# Integrated_Preamp_Sch.net
KiCad netlist of a schematic drawn in Altium Designer
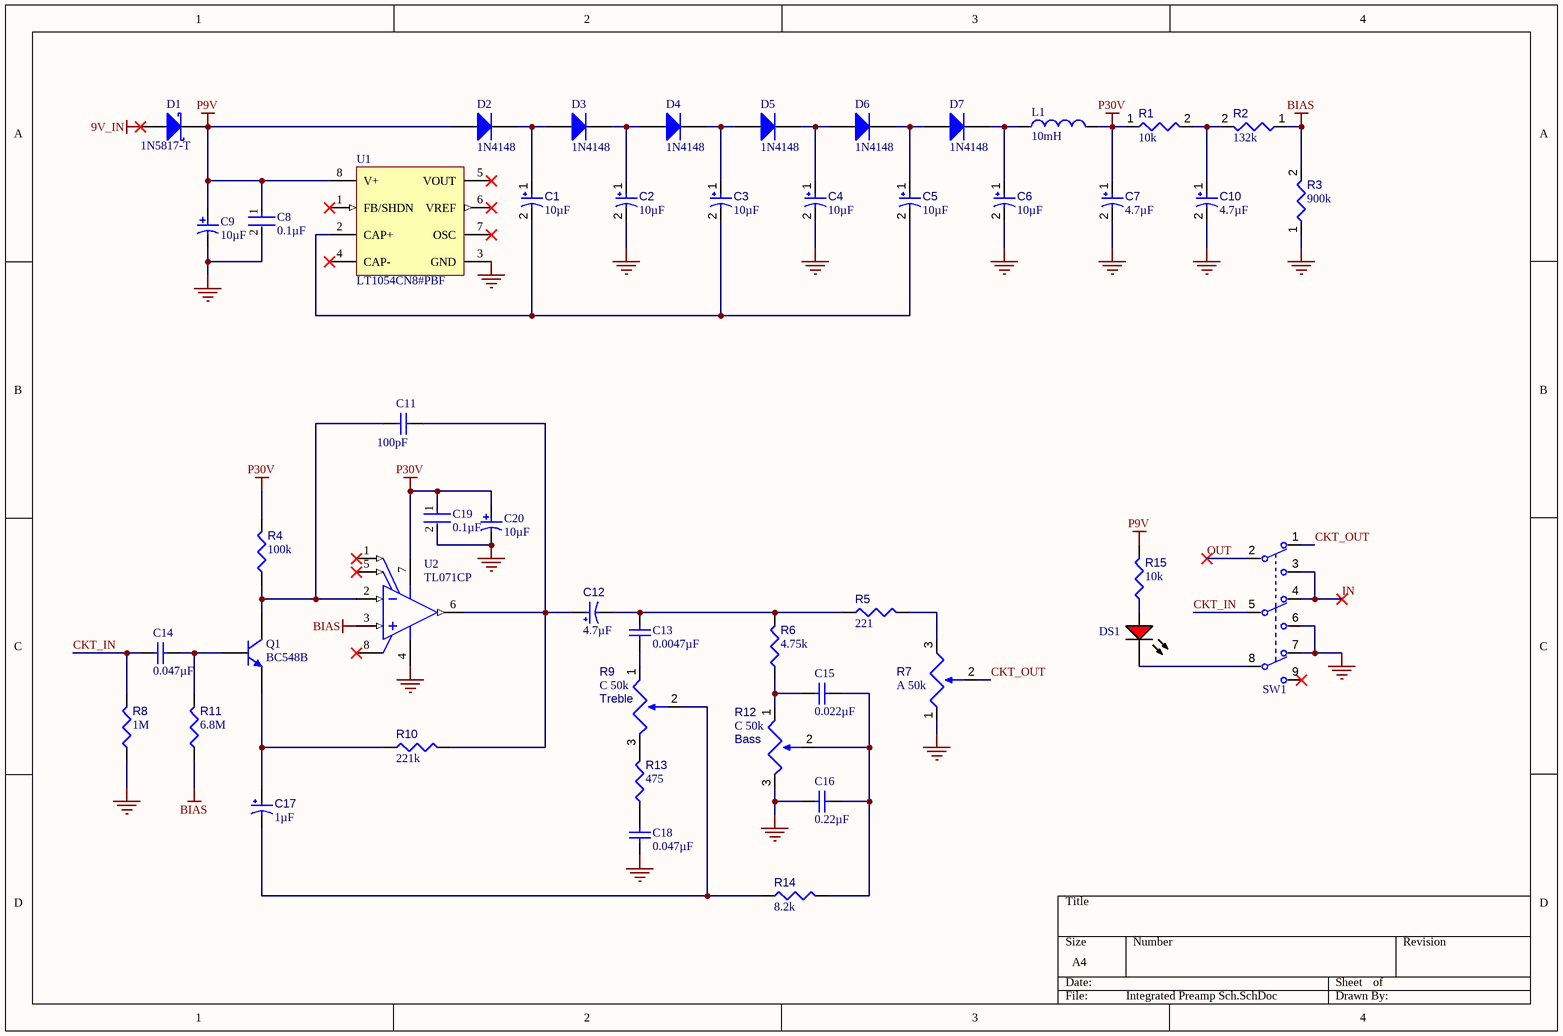
[diagram p0: Integrated Preamp Sch.SchDoc]

(export (version "E")
  (design (tool "Eeschema 10.0.6"))
  (components
    (comp (ref "C1")
      (value "10µF")
      (footprint "CAPPR55-200-1100X500X1200")
      (description "Aluminum Electrolytic Capacitor, 10 uF, +/- 20%, 50 V, -40 to 85 degC, 2-Pin THD, RoHS, Bulk")
      (fields (field (name "MANUFACTURER") "Panasonic") (field (name "TOLERANCE") "20%"))
      (libsource (lib "Andy R - Ferris State University") (part "CAP-P-2"))
    )
    (comp (ref "C2")
      (value "10µF")
      (footprint "CAPPR55-200-1100X500X1200")
      (description "Aluminum Electrolytic Capacitor, 10 uF, +/- 20%, 50 V, -40 to 85 degC, 2-Pin THD, RoHS, Bulk")
      (fields (field (name "MANUFACTURER") "Panasonic") (field (name "TOLERANCE") "20%"))
      (libsource (lib "Andy R - Ferris State University") (part "CAP-P-2"))
    )
    (comp (ref "C3")
      (value "10µF")
      (footprint "CAPPR55-200-1100X500X1200")
      (description "Aluminum Electrolytic Capacitor, 10 uF, +/- 20%, 50 V, -40 to 85 degC, 2-Pin THD, RoHS, Bulk")
      (fields (field (name "MANUFACTURER") "Panasonic") (field (name "TOLERANCE") "20%"))
      (libsource (lib "Andy R - Ferris State University") (part "CAP-P-2"))
    )
    (comp (ref "C4")
      (value "10µF")
      (footprint "CAPPR55-200-1100X500X1200")
      (description "Aluminum Electrolytic Capacitor, 10 uF, +/- 20%, 50 V, -40 to 85 degC, 2-Pin THD, RoHS, Bulk")
      (fields (field (name "MANUFACTURER") "Panasonic") (field (name "TOLERANCE") "20%"))
      (libsource (lib "Andy R - Ferris State University") (part "CAP-P-2"))
    )
    (comp (ref "C5")
      (value "10µF")
      (footprint "CAPPR55-200-1100X500X1200")
      (description "Aluminum Electrolytic Capacitor, 10 uF, +/- 20%, 50 V, -40 to 85 degC, 2-Pin THD, RoHS, Bulk")
      (fields (field (name "MANUFACTURER") "Panasonic") (field (name "TOLERANCE") "20%"))
      (libsource (lib "Andy R - Ferris State University") (part "CAP-P-2"))
    )
    (comp (ref "C6")
      (value "10µF")
      (footprint "CAPPR55-200-1100X500X1200")
      (description "Aluminum Electrolytic Capacitor, 10 uF, +/- 20%, 50 V, -40 to 85 degC, 2-Pin THD, RoHS, Bulk")
      (fields (field (name "MANUFACTURER") "Panasonic") (field (name "TOLERANCE") "20%"))
      (libsource (lib "Andy R - Ferris State University") (part "CAP-P-2"))
    )
    (comp (ref "C7")
      (value "4.7µF")
      (footprint "CAPPR55-200-1100X500X1200")
      (description "Aluminum Electrolytic Capacitor, 4.7 uF, +/- 20%, 50 V, -40 to 85 degC, 2-Pin THD, RoHS, Bulk")
      (fields (field (name "MANUFACTURER") "Panasonic") (field (name "TOLERANCE") "20%"))
      (libsource (lib "Andy R - Ferris State University") (part "CAP-P-2"))
    )
    (comp (ref "C8")
      (value "0.1µF")
      (footprint "FP-C322C104K5R5TA-MFG")
      (description "CAP CER 0.1UF 50V X7R RADIAL")
      (fields (field (name "TOLERANCE") "10%") (field (name "VOLTAGE") "50V"))
      (libsource (lib "Altium Content Vault") (part "b4654b650e69147ec39a6b967a45e02"))
    )
    (comp (ref "C9")
      (value "10µF")
      (footprint "AVX-TAP475K016SCS")
      (description "Dipped Radial Capacitor, 4.7 uF, +/- 10%, 16 V, -55 to 125 degC, RoHS, Bulk")
      (fields (field (name "TOLERANCE") "10%") (field (name "VOLTAGE") "16V"))
      (libsource (lib "Altium Content Vault") (part "CAP-P-2"))
    )
    (comp (ref "C10")
      (value "4.7µF")
      (footprint "CAPPR55-200-1100X500X1200")
      (description "Aluminum Electrolytic Capacitor, 4.7 uF, +/- 20%, 50 V, -40 to 85 degC, 2-Pin THD, RoHS, Bulk")
      (fields (field (name "MANUFACTURER") "Panasonic") (field (name "TOLERANCE") "20%"))
      (libsource (lib "Andy R - Ferris State University") (part "CAP-P-2"))
    )
    (comp (ref "C11")
      (value "MKS2D034701E00KSSD")
      (footprint "WIMA-MKS2D034701E00")
      (fields (field (name "MANUFACTURER") "Wima") (field (name "CAPACITANCE") "100pF"))
      (libsource (lib "Altium Content Vault") (part "CAP-NP-2"))
    )
    (comp (ref "C12")
      (value "4.7µF")
      (footprint "CAPPR55-200-1100X500X1200")
      (description "Aluminum Electrolytic Capacitor, 4.7 uF, +/- 20%, 50 V, -40 to 85 degC, 2-Pin THD, RoHS, Bulk")
      (fields (field (name "MANUFACTURER") "Panasonic") (field (name "TOLERANCE") "20%"))
      (libsource (lib "") (part "CAP-P-2_1"))
    )
    (comp (ref "C13")
      (value "CMP-2000-06717-1")
      (footprint "WIMA-MKS2D024701A00KSSD")
      (fields (field (name "MANUFACTURER") "Wima") (field (name "CAPACITANCE") "0.0047µF"))
      (libsource (lib "Integrated Preamp Sch Lib") (part "CMP-2000-06717-1"))
    )
    (comp (ref "C14")
      (value ".047µF")
      (footprint "WIMA-MKS2D024701A00KSSD")
      (fields (field (name "MANUFACTURER") "Wima") (field (name "CAPACITANCE") "0.047µF"))
      (libsource (lib "Integrated Preamp Sch Lib") (part "CMP-2000-06717-1"))
    )
    (comp (ref "C15")
      (value "CMP-2000-06717-1")
      (footprint "WIMA-MKS2D024701A00KSSD")
      (fields (field (name "MANUFACTURER") "Wima") (field (name "CAPACITANCE") "0.022µF"))
      (libsource (lib "Integrated Preamp Sch Lib") (part "CMP-2000-06717-1"))
    )
    (comp (ref "C16")
      (value "CMP-2000-06717-1")
      (footprint "WIMA-MKS2D024701A00KSSD")
      (fields (field (name "MANUFACTURER") "Wima") (field (name "CAPACITANCE") "0.22µF"))
      (libsource (lib "Integrated Preamp Sch Lib") (part "CMP-2000-06717-1"))
    )
    (comp (ref "C17")
      (value "1µF")
      (footprint "CAPPR55-200-1100X500X1200")
      (description "Aluminum Electrolytic Capacitor, 1 uF, +/- 20%, 50 V, -55 to 105 degC, 2-Pin THD, RoHS, Bulk")
      (fields (field (name "TOLERANCE") "20%") (field (name "MANUFACTURER") "Panasonic"))
      (libsource (lib "") (part "CAP-P-2_2"))
    )
    (comp (ref "C18")
      (value "CMP-2000-06717-1")
      (footprint "WIMA-MKS2D024701A00KSSD")
      (fields (field (name "MANUFACTURER") "Wima") (field (name "CAPACITANCE") "0.047µF"))
      (libsource (lib "Integrated Preamp Sch Lib") (part "CMP-2000-06717-1"))
    )
    (comp (ref "C19")
      (value "0.1µF")
      (footprint "FP-C322C104K5R5TA-MFG")
      (description "CAP CER 0.1UF 50V X7R RADIAL")
      (fields (field (name "TOLERANCE") "10%") (field (name "VOLTAGE") "50V"))
      (libsource (lib "Altium Content Vault") (part "b4654b650e69147ec39a6b967a45e02"))
    )
    (comp (ref "C20")
      (value "10µF")
      (footprint "AVX-TAP475K016SCS")
      (description "Dipped Radial Capacitor, 4.7 uF, +/- 10%, 16 V, -55 to 125 degC, RoHS, Bulk")
      (fields (field (name "TOLERANCE") "10%") (field (name "VOLTAGE") "16V"))
      (libsource (lib "Altium Content Vault") (part "CAP-P-2"))
    )
    (comp (ref "D1")
      (value "1N5817-T")
      (footprint "DIOD-DO-41-P-2")
      (description "Schottky Barrier Rectifier, 1 A, 20 V, -65 to 125 degC, 2-Pin DO-41, RoHS, Tape and Reel")
      (fields (field (name "MANUFACTURER") "DiodesIncorporated"))
      (libsource (lib "Altium Content Vault") (part "DSKY-AK-2"))
    )
    (comp (ref "D2")
      (value "1N4148")
      (footprint "NXP-SOD27-2_V")
      (description "High Speed Diode, 100 V, 0.45 A, -65 to 175 degC, 2-Pin SOD27, RoHS, Bulk")
      (fields (field (name "POWER") "500mW") (field (name "MANUFACTURER") "Fairchild"))
      (libsource (lib "Andy R - Ferris State University") (part "D-AK-2"))
    )
    (comp (ref "D3")
      (value "1N4148")
      (footprint "NXP-SOD27-2_V")
      (description "High Speed Diode, 100 V, 0.45 A, -65 to 175 degC, 2-Pin SOD27, RoHS, Bulk")
      (fields (field (name "POWER") "500mW") (field (name "MANUFACTURER") "Fairchild"))
      (libsource (lib "Andy R - Ferris State University") (part "D-AK-2"))
    )
    (comp (ref "D4")
      (value "1N4148")
      (footprint "NXP-SOD27-2_V")
      (description "High Speed Diode, 100 V, 0.45 A, -65 to 175 degC, 2-Pin SOD27, RoHS, Bulk")
      (fields (field (name "POWER") "500mW") (field (name "MANUFACTURER") "Fairchild"))
      (libsource (lib "Andy R - Ferris State University") (part "D-AK-2"))
    )
    (comp (ref "D5")
      (value "1N4148")
      (footprint "NXP-SOD27-2_V")
      (description "High Speed Diode, 100 V, 0.45 A, -65 to 175 degC, 2-Pin SOD27, RoHS, Bulk")
      (fields (field (name "POWER") "500mW") (field (name "MANUFACTURER") "Fairchild"))
      (libsource (lib "Andy R - Ferris State University") (part "D-AK-2"))
    )
    (comp (ref "D6")
      (value "1N4148")
      (footprint "NXP-SOD27-2_V")
      (description "High Speed Diode, 100 V, 0.45 A, -65 to 175 degC, 2-Pin SOD27, RoHS, Bulk")
      (fields (field (name "POWER") "500mW") (field (name "MANUFACTURER") "Fairchild"))
      (libsource (lib "Andy R - Ferris State University") (part "D-AK-2"))
    )
    (comp (ref "D7")
      (value "1N4148")
      (footprint "NXP-SOD27-2_V")
      (description "High Speed Diode, 100 V, 0.45 A, -65 to 175 degC, 2-Pin SOD27, RoHS, Bulk")
      (fields (field (name "POWER") "500mW") (field (name "MANUFACTURER") "Fairchild"))
      (libsource (lib "Andy R - Ferris State University") (part "D-AK-2"))
    )
    (comp (ref "DS1")
      (value "LTL-1CHE")
      (footprint "INDPR60-254-520X380X650")
      (description "LED Uni-Color Red, 100 mW, 30 mA, -55 to 100 degC, 2-Pin THD, RoHS, Bulk")
      (fields (field (name "MANUFACTURER") "Lite-On"))
      (libsource (lib "Andy R - Ferris State University") (part "LED-RED-AK-2"))
    )
    (comp (ref "L1")
      (value "10mH")
      (footprint "EPCS-B78108S-2_V1")
      (description "RF Choke, 470 uH +/- 5%, 170 mA, Dia 4 mm, Length 9.2 mm, Axial Leads, RoHS, Tape and Reel")
      (fields (field (name "MANUFACTURER") "EPCOS") (field (name "TOLERANCE") "+/- 5%"))
      (libsource (lib "Altium Content Vault") (part "EPCS-IND-2"))
    )
    (comp (ref "Q1")
      (value "BC548B")
      (footprint "ONSC-TO-92-3-29-11")
      (description "Amplifier Transistor, NPN Silicon, 3-Pin TO-92, Bulk Box")
      (fields (field (name "MANUFACTURER") "On Semiconductor"))
      (libsource (lib "Altium Content Vault") (part "ONSC-NPN-C1B2E3-3"))
    )
    (comp (ref "R1")
      (value "10k")
      (footprint "RESA60-630X240")
      (description "Axial Resistor, 10 KOhm, +/- 1%, 0.25 W, -55 to 155 degC, 2-Pin THD, RoHS, Bulk")
      (fields (field (name "TOLERANCE") "1%") (field (name "POWER") "250mW"))
      (libsource (lib "Andy R - Ferris State University") (part "RES-2"))
    )
    (comp (ref "R2")
      (value "132k")
      (footprint "RESA60-630X240")
      (description "Axial Resistor, 100 KOhm, +/- 1%, 0.25 W, -55 to 155 degC, 2-Pin THD, RoHS, Bulk")
      (fields (field (name "POWER") "250mW") (field (name "MANUFACTURER") "Yageo"))
      (libsource (lib "Andy R - Ferris State University") (part "RES-2"))
    )
    (comp (ref "R3")
      (value "900k")
      (footprint "RESA60-630X240")
      (description "Axial Resistor, 1 MOhm, +/- 1%, 250 mW, -55 to 155 degC, 2-Pin THD, RoHS, Bulk")
      (fields (field (name "TOLERANCE") "1%") (field (name "MANUFACTURER") "Yageo"))
      (libsource (lib "Andy R - Ferris State University") (part "RES-2"))
    )
    (comp (ref "R4")
      (value "100k")
      (footprint "RESA60-630X240")
      (description "Axial Resistor, 100 KOhm, +/- 1%, 0.25 W, -55 to 155 degC, 2-Pin THD, RoHS, Bulk")
      (fields (field (name "POWER") "250mW") (field (name "MANUFACTURER") "Yageo"))
      (libsource (lib "") (part "RES-2_1"))
    )
    (comp (ref "R5")
      (value "221")
      (footprint "RESA60-630X240")
      (description "Axial Resistor, 221 Ohm, +/- 1%, 250 mW, -55 to 155 degC, 2-Pin THD, RoHS, Bulk")
      (fields (field (name "POWER") "250mW") (field (name "TOLERANCE") "1%"))
      (libsource (lib "") (part "RES-2_1"))
    )
    (comp (ref "R6")
      (value "4.75k")
      (footprint "RESA60-630X240")
      (description "Axial Resistor, 4.75 KOhm, +/- 1%, 0.25 W, -55 to 155 degC, 2-Pin THD, RoHS, Bulk")
      (fields (field (name "POWER") "250mW") (field (name "TOLERANCE") "1%"))
      (libsource (lib "") (part "RES-2_1"))
    )
    (comp (ref "R7")
      (value "A 50k")
      (footprint "PCB Mount Potentiometer")
      (fields (field (name "Comment") "Potentiometer"))
      (libsource (lib "Integrated Preamp Sch Lib") (part "Potentiometer"))
    )
    (comp (ref "R8")
      (value "1M")
      (footprint "RESA60-630X240")
      (description "Axial Resistor, 4.75 KOhm, +/- 1%, 0.25 W, -55 to 155 degC, 2-Pin THD, RoHS, Bulk")
      (fields (field (name "POWER") "250mW") (field (name "TOLERANCE") "1%"))
      (libsource (lib "") (part "RES-2_1"))
    )
    (comp (ref "R9")
      (value "Treble")
      (footprint "PCB Mount Potentiometer")
      (fields (field (name "ALTIUM_VALUE") "C 50k"))
      (libsource (lib "Integrated Preamp Sch Lib") (part "Potentiometer"))
    )
    (comp (ref "R10")
      (value "221k")
      (footprint "RESA60-630X240")
      (description "Axial Resistor, 221 KOhm, +/- 1%, 0.25 W, -55 to 155 degC, 2-Pin THD, RoHS, Bulk")
      (fields (field (name "POWER") "250mW") (field (name "TOLERANCE") "1%"))
      (libsource (lib "") (part "RES-2_1"))
    )
    (comp (ref "R11")
      (value "6.8M")
      (footprint "RESA60-630X240")
      (description "Axial Resistor, 6.8 MOhm, +/- 1%, 250 mW, -55 to 155 degC, 2-Pin THD, RoHS, Bulk")
      (fields (field (name "TOLERANCE") "1%") (field (name "MANUFACTURER") "Yageo"))
      (libsource (lib "") (part "RES-2_1"))
    )
    (comp (ref "R12")
      (value "Bass")
      (footprint "PCB Mount Potentiometer")
      (fields (field (name "ALTIUM_VALUE") "C 50k"))
      (libsource (lib "Integrated Preamp Sch Lib") (part "Potentiometer"))
    )
    (comp (ref "R13")
      (value "475")
      (footprint "RESA60-630X240")
      (description "Axial Resistor, 475 Ohm, +/- 1%, 0.25 W, -55 to 155 degC, 2-Pin THD, RoHS, Bulk")
      (fields (field (name "MANUFACTURER") "Yageo") (field (name "TOLERANCE") "1%"))
      (libsource (lib "") (part "RES-2_1"))
    )
    (comp (ref "R14")
      (value "8.2k")
      (footprint "RESA60-630X240")
      (description "Axial Resistor, 4.75 KOhm, +/- 1%, 0.25 W, -55 to 155 degC, 2-Pin THD, RoHS, Bulk")
      (fields (field (name "POWER") "250mW") (field (name "TOLERANCE") "1%"))
      (libsource (lib "") (part "RES-2_1"))
    )
    (comp (ref "R15")
      (value "10k")
      (footprint "RESA60-630X240")
      (description "Axial Resistor, 10 KOhm, +/- 1%, 0.25 W, -55 to 155 degC, 2-Pin THD, RoHS, Bulk")
      (fields (field (name "TOLERANCE") "1%") (field (name "POWER") "250mW"))
      (libsource (lib "") (part "RES-2_1"))
    )
    (comp (ref "SW1")
      (value "MPG306F")
      (footprint "3PDT Stomp")
      (description "SWITCH PUSHBUTTON 3PDT 6A 125V")
      (libsource (lib "Integrated Preamp Sch Lib") (part "CMP-03402-000028-1"))
    )
    (comp (ref "U1")
      (value "LT1054CN8#PBF")
      (footprint "LT-N8-8")
      (fields (field (name "MANUFACTURER") "Linear Technology"))
      (libsource (lib "Altium Content Vault") (part "LT-LT1054X-8"))
    )
    (comp (ref "U2")
      (value "TL071CP")
      (footprint "P0008A")
      (fields (field (name "MANUFACTURER") "Texas Instruments"))
      (libsource (lib "Altium Content Vault") (part "TI-AMP-S5-2-8"))
    )
  )
  (nets
    (net (code "1") (name "/CKT_IN") (class "Default")
      (node (ref "C14") (pin "1") (pinfunction "1_1") (pintype "passive"))
      (node (ref "R8") (pin "2") (pinfunction "2_2") (pintype "passive"))
      (node (ref "SW1") (pin "5") (pinfunction "5_5") (pintype "passive"))
    )
    (net (code "2") (name "/CKT_OUT") (class "Default")
      (node (ref "R7") (pin "2") (pinfunction "2_2") (pintype "passive"))
      (node (ref "SW1") (pin "1") (pinfunction "1_1") (pintype "passive"))
    )
    (net (code "3") (name "/IN") (class "Default")
      (node (ref "SW1") (pin "3") (pinfunction "3_3") (pintype "passive"))
      (node (ref "SW1") (pin "4") (pinfunction "4_4") (pintype "passive"))
    )
    (net (code "4") (name "/OUT") (class "Default")
      (node (ref "SW1") (pin "2") (pinfunction "2_2") (pintype "passive+no_connect"))
    )
    (net (code "5") (name "9V_IN") (class "Default")
      (node (ref "D1") (pin "1") (pinfunction "A_1") (pintype "passive"))
    )
    (net (code "6") (name "BIAS") (class "Default")
      (node (ref "R11") (pin "1") (pinfunction "1_1") (pintype "passive"))
      (node (ref "R2") (pin "1") (pinfunction "1_1") (pintype "passive"))
      (node (ref "R3") (pin "2") (pinfunction "2_2") (pintype "passive"))
      (node (ref "U2") (pin "3") (pinfunction "IN+_3") (pintype "input"))
    )
    (net (code "7") (name "GND") (class "Default")
      (node (ref "C10") (pin "2") (pinfunction "2_2") (pintype "passive"))
      (node (ref "C16") (pin "1") (pinfunction "1_1") (pintype "passive"))
      (node (ref "C18") (pin "1") (pinfunction "1_1") (pintype "passive"))
      (node (ref "C19") (pin "2") (pinfunction "2_2") (pintype "passive"))
      (node (ref "C2") (pin "2") (pinfunction "2_2") (pintype "passive"))
      (node (ref "C20") (pin "2") (pinfunction "2_2") (pintype "passive"))
      (node (ref "C4") (pin "2") (pinfunction "2_2") (pintype "passive"))
      (node (ref "C6") (pin "2") (pinfunction "2_2") (pintype "passive"))
      (node (ref "C7") (pin "2") (pinfunction "2_2") (pintype "passive"))
      (node (ref "C8") (pin "2") (pinfunction "2_2") (pintype "passive"))
      (node (ref "C9") (pin "2") (pinfunction "2_2") (pintype "passive"))
      (node (ref "R12") (pin "3") (pinfunction "3_3") (pintype "passive"))
      (node (ref "R3") (pin "1") (pinfunction "1_1") (pintype "passive"))
      (node (ref "R7") (pin "1") (pinfunction "1_1") (pintype "passive"))
      (node (ref "R8") (pin "1") (pinfunction "1_1") (pintype "passive"))
      (node (ref "SW1") (pin "6") (pinfunction "6_6") (pintype "passive"))
      (node (ref "SW1") (pin "7") (pinfunction "7_7") (pintype "passive"))
      (node (ref "U1") (pin "3") (pinfunction "GND_3") (pintype "power_in"))
      (node (ref "U2") (pin "4") (pinfunction "VCC-_4") (pintype "power_in"))
    )
    (net (code "8") (name "Net-(C10-Pad1)") (class "Default")
      (node (ref "C10") (pin "1") (pinfunction "1_1") (pintype "passive"))
      (node (ref "R1") (pin "2") (pinfunction "2_2") (pintype "passive"))
      (node (ref "R2") (pin "2") (pinfunction "2_2") (pintype "passive"))
    )
    (net (code "9") (name "Net-(C12-Pad2)") (class "Default")
      (node (ref "C12") (pin "2") (pinfunction "2_2") (pintype "passive"))
      (node (ref "C13") (pin "2") (pinfunction "2_2") (pintype "passive"))
      (node (ref "R5") (pin "1") (pinfunction "1_1") (pintype "passive"))
      (node (ref "R6") (pin "2") (pinfunction "2_2") (pintype "passive"))
    )
    (net (code "10") (name "Net-(C13-Pad1)") (class "Default")
      (node (ref "C13") (pin "1") (pinfunction "1_1") (pintype "passive"))
      (node (ref "R9") (pin "1") (pinfunction "1_1") (pintype "passive"))
    )
    (net (code "11") (name "Net-(C15-Pad1)") (class "Default")
      (node (ref "C15") (pin "1") (pinfunction "1_1") (pintype "passive"))
      (node (ref "R12") (pin "1") (pinfunction "1_1") (pintype "passive"))
      (node (ref "R6") (pin "1") (pinfunction "1_1") (pintype "passive"))
    )
    (net (code "12") (name "Net-(C15-Pad2)") (class "Default")
      (node (ref "C15") (pin "2") (pinfunction "2_2") (pintype "passive"))
      (node (ref "C16") (pin "2") (pinfunction "2_2") (pintype "passive"))
      (node (ref "R12") (pin "2") (pinfunction "2_2") (pintype "passive"))
      (node (ref "R14") (pin "2") (pinfunction "2_2") (pintype "passive"))
    )
    (net (code "13") (name "Net-(C17-Pad2)") (class "Default")
      (node (ref "C17") (pin "2") (pinfunction "2_2") (pintype "passive"))
      (node (ref "R14") (pin "1") (pinfunction "1_1") (pintype "passive"))
      (node (ref "R9") (pin "2") (pinfunction "2_2") (pintype "passive"))
    )
    (net (code "14") (name "Net-(C18-Pad2)") (class "Default")
      (node (ref "C18") (pin "2") (pinfunction "2_2") (pintype "passive"))
      (node (ref "R13") (pin "1") (pinfunction "1_1") (pintype "passive"))
    )
    (net (code "15") (name "Net-(D2-K)") (class "Default")
      (node (ref "C1") (pin "1") (pinfunction "1_1") (pintype "passive"))
      (node (ref "D2") (pin "2") (pinfunction "K_2") (pintype "passive"))
      (node (ref "D3") (pin "1") (pinfunction "A_1") (pintype "passive"))
    )
    (net (code "16") (name "Net-(D3-K)") (class "Default")
      (node (ref "C2") (pin "1") (pinfunction "1_1") (pintype "passive"))
      (node (ref "D3") (pin "2") (pinfunction "K_2") (pintype "passive"))
      (node (ref "D4") (pin "1") (pinfunction "A_1") (pintype "passive"))
    )
    (net (code "17") (name "Net-(D4-K)") (class "Default")
      (node (ref "C3") (pin "1") (pinfunction "1_1") (pintype "passive"))
      (node (ref "D4") (pin "2") (pinfunction "K_2") (pintype "passive"))
      (node (ref "D5") (pin "1") (pinfunction "A_1") (pintype "passive"))
    )
    (net (code "18") (name "Net-(D5-K)") (class "Default")
      (node (ref "C4") (pin "1") (pinfunction "1_1") (pintype "passive"))
      (node (ref "D5") (pin "2") (pinfunction "K_2") (pintype "passive"))
      (node (ref "D6") (pin "1") (pinfunction "A_1") (pintype "passive"))
    )
    (net (code "19") (name "Net-(D6-K)") (class "Default")
      (node (ref "C5") (pin "1") (pinfunction "1_1") (pintype "passive"))
      (node (ref "D6") (pin "2") (pinfunction "K_2") (pintype "passive"))
      (node (ref "D7") (pin "1") (pinfunction "A_1") (pintype "passive"))
    )
    (net (code "20") (name "Net-(D7-K)") (class "Default")
      (node (ref "C6") (pin "1") (pinfunction "1_1") (pintype "passive"))
      (node (ref "D7") (pin "2") (pinfunction "K_2") (pintype "passive"))
      (node (ref "L1") (pin "1") (pinfunction "1_1") (pintype "passive"))
    )
    (net (code "21") (name "Net-(DS1-A)") (class "Default")
      (node (ref "DS1") (pin "1") (pinfunction "A_1") (pintype "passive"))
      (node (ref "R15") (pin "1") (pinfunction "1_1") (pintype "passive"))
    )
    (net (code "22") (name "Net-(DS1-K)") (class "Default")
      (node (ref "DS1") (pin "2") (pinfunction "K_2") (pintype "passive"))
      (node (ref "SW1") (pin "8") (pinfunction "8_8") (pintype "passive"))
    )
    (net (code "23") (name "Net-(Q1-B)") (class "Default")
      (node (ref "C14") (pin "2") (pinfunction "2_2") (pintype "passive"))
      (node (ref "Q1") (pin "2") (pinfunction "B_2") (pintype "passive"))
      (node (ref "R11") (pin "2") (pinfunction "2_2") (pintype "passive"))
    )
    (net (code "24") (name "Net-(Q1-C)") (class "Default")
      (node (ref "C11") (pin "1") (pinfunction "1_1") (pintype "passive"))
      (node (ref "Q1") (pin "1") (pinfunction "C_1") (pintype "passive"))
      (node (ref "R4") (pin "1") (pinfunction "1_1") (pintype "passive"))
      (node (ref "U2") (pin "2") (pinfunction "IN-_2") (pintype "input"))
    )
    (net (code "25") (name "Net-(Q1-E)") (class "Default")
      (node (ref "C17") (pin "1") (pinfunction "1_1") (pintype "passive"))
      (node (ref "Q1") (pin "3") (pinfunction "E_3") (pintype "passive"))
      (node (ref "R10") (pin "1") (pinfunction "1_1") (pintype "passive"))
    )
    (net (code "26") (name "Net-(R5-Pad2)") (class "Default")
      (node (ref "R5") (pin "2") (pinfunction "2_2") (pintype "passive"))
      (node (ref "R7") (pin "3") (pinfunction "3_3") (pintype "passive"))
    )
    (net (code "27") (name "Net-(R13-Pad2)") (class "Default")
      (node (ref "R13") (pin "2") (pinfunction "2_2") (pintype "passive"))
      (node (ref "R9") (pin "3") (pinfunction "3_3") (pintype "passive"))
    )
    (net (code "28") (name "Net-(U1-CAP+)") (class "Default")
      (node (ref "C1") (pin "2") (pinfunction "2_2") (pintype "passive"))
      (node (ref "C3") (pin "2") (pinfunction "2_2") (pintype "passive"))
      (node (ref "C5") (pin "2") (pinfunction "2_2") (pintype "passive"))
      (node (ref "U1") (pin "2") (pinfunction "CAP+_2") (pintype "passive"))
    )
    (net (code "29") (name "Net-(U2-OUT)") (class "Default")
      (node (ref "C11") (pin "2") (pinfunction "2_2") (pintype "passive"))
      (node (ref "C12") (pin "1") (pinfunction "1_1") (pintype "passive"))
      (node (ref "R10") (pin "2") (pinfunction "2_2") (pintype "passive"))
      (node (ref "U2") (pin "6") (pinfunction "OUT_6") (pintype "output"))
    )
    (net (code "30") (name "P9V") (class "Default")
      (node (ref "C8") (pin "1") (pinfunction "1_1") (pintype "passive"))
      (node (ref "C9") (pin "1") (pinfunction "1_1") (pintype "passive"))
      (node (ref "D1") (pin "2") (pinfunction "K_2") (pintype "passive"))
      (node (ref "D2") (pin "1") (pinfunction "A_1") (pintype "passive"))
      (node (ref "R15") (pin "2") (pinfunction "2_2") (pintype "passive"))
      (node (ref "U1") (pin "8") (pinfunction "V+_8") (pintype "power_in"))
    )
    (net (code "31") (name "P30V") (class "Default")
      (node (ref "C19") (pin "1") (pinfunction "1_1") (pintype "passive"))
      (node (ref "C20") (pin "1") (pinfunction "1_1") (pintype "passive"))
      (node (ref "C7") (pin "1") (pinfunction "1_1") (pintype "passive"))
      (node (ref "L1") (pin "2") (pinfunction "2_2") (pintype "passive"))
      (node (ref "R1") (pin "1") (pinfunction "1_1") (pintype "passive"))
      (node (ref "R4") (pin "2") (pinfunction "2_2") (pintype "passive"))
      (node (ref "U2") (pin "7") (pinfunction "VCC+_7") (pintype "power_in"))
    )
    (net (code "32") (name "unconnected-(SW1-Pad9)") (class "Default")
      (node (ref "SW1") (pin "9") (pinfunction "9_9") (pintype "passive+no_connect"))
    )
    (net (code "33") (name "unconnected-(U1-CAP--Pad4)") (class "Default")
      (node (ref "U1") (pin "4") (pinfunction "CAP-_4") (pintype "passive+no_connect"))
    )
    (net (code "34") (name "unconnected-(U1-FB{slash}SHDN-Pad1)") (class "Default")
      (node (ref "U1") (pin "1") (pinfunction "FB/SHDN_1") (pintype "input+no_connect"))
    )
    (net (code "35") (name "unconnected-(U1-OSC-Pad7)") (class "Default")
      (node (ref "U1") (pin "7") (pinfunction "OSC_7") (pintype "passive+no_connect"))
    )
    (net (code "36") (name "unconnected-(U1-VOUT-Pad5)") (class "Default")
      (node (ref "U1") (pin "5") (pinfunction "VOUT_5") (pintype "power_in+no_connect"))
    )
    (net (code "37") (name "unconnected-(U1-VREF-Pad6)") (class "Default")
      (node (ref "U1") (pin "6") (pinfunction "VREF_6") (pintype "output+no_connect"))
    )
    (net (code "38") (name "unconnected-(U2-NC-Pad8)") (class "Default")
      (node (ref "U2") (pin "8") (pinfunction "NC_8") (pintype "passive+no_connect"))
    )
    (net (code "39") (name "unconnected-(U2-OFFSET_N1-Pad1)") (class "Default")
      (node (ref "U2") (pin "1") (pinfunction "OFFSET_N1_1") (pintype "input+no_connect"))
    )
    (net (code "40") (name "unconnected-(U2-OFFSET_N2-Pad5)") (class "Default")
      (node (ref "U2") (pin "5") (pinfunction "OFFSET_N2_5") (pintype "input+no_connect"))
    )
  )
)
